# dc-dc_eth.net
KiCad netlist of a schematic drawn in Altium Designer
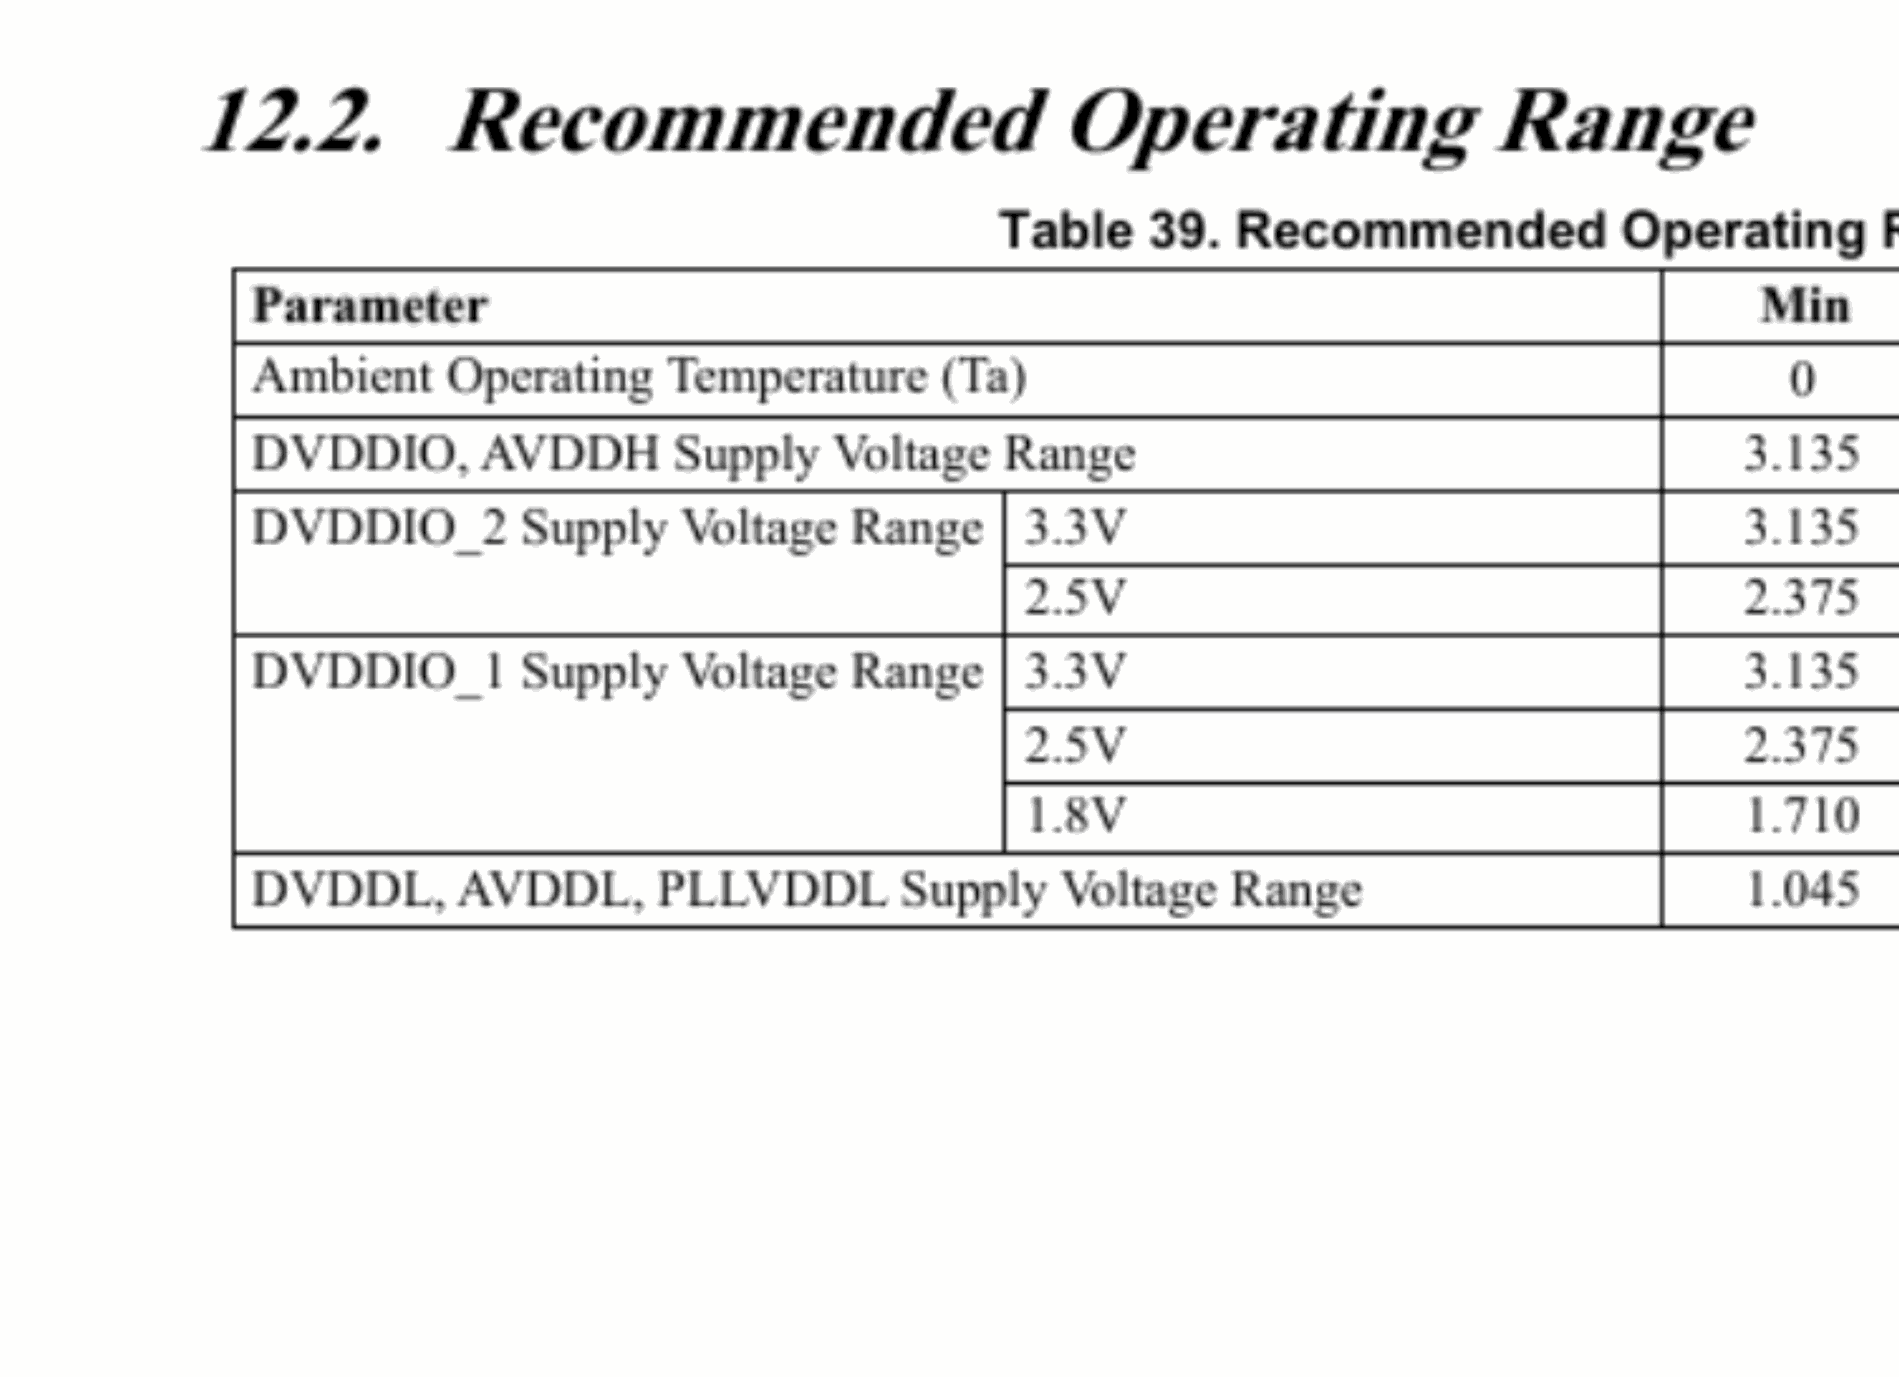
[diagram p0: dc-dc_eth.SchDoc, top left]
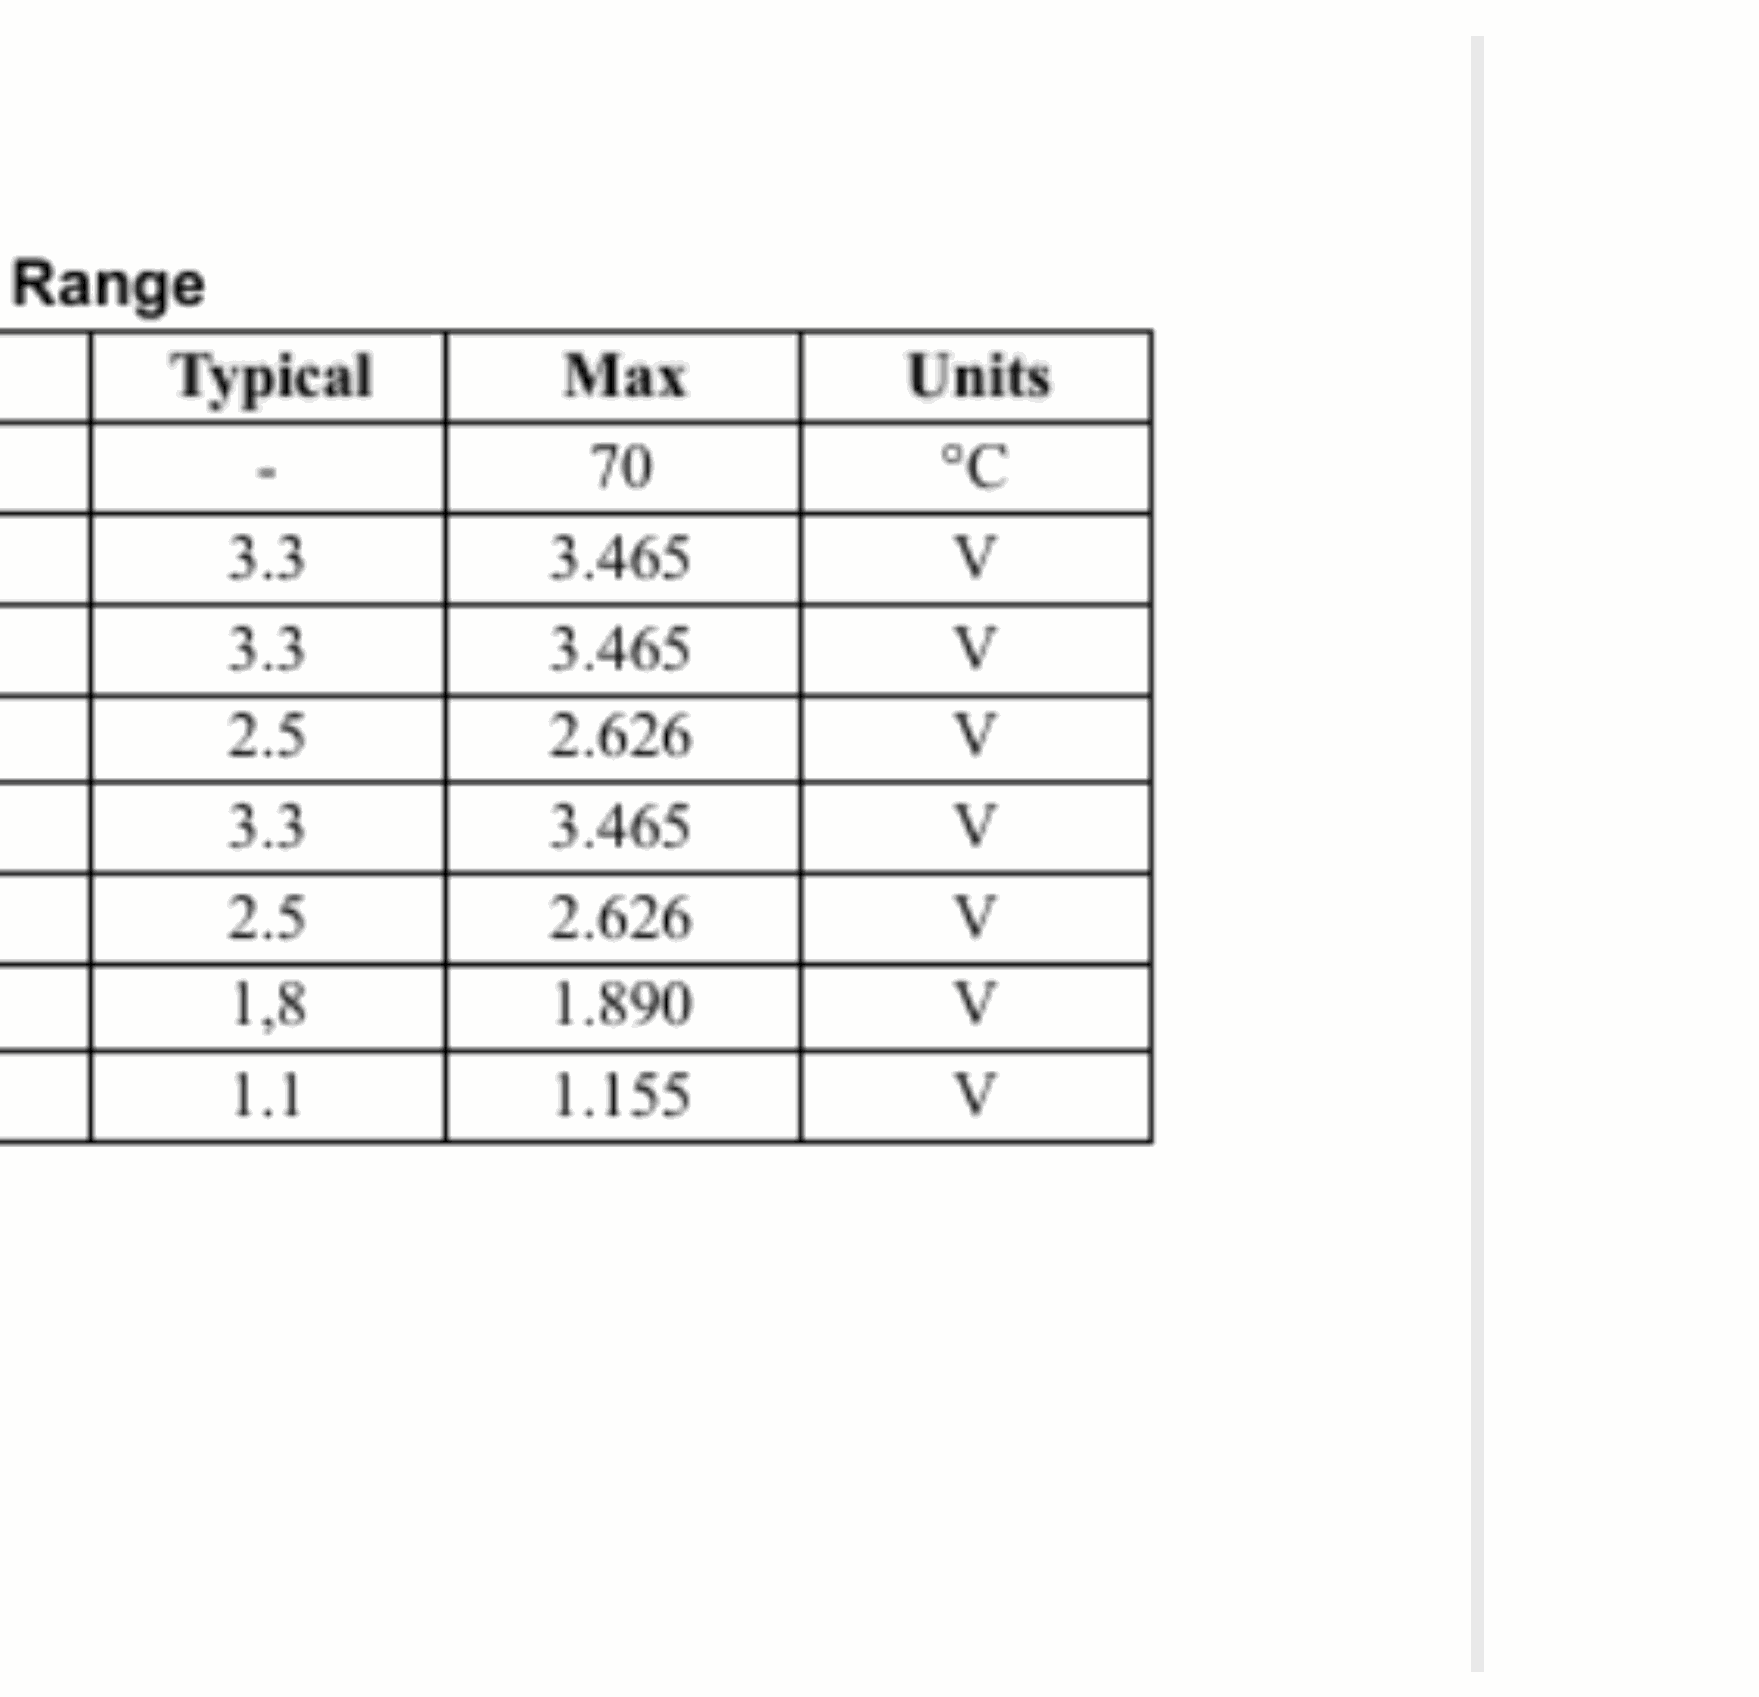
[diagram p1: dc-dc_eth.SchDoc, top right]
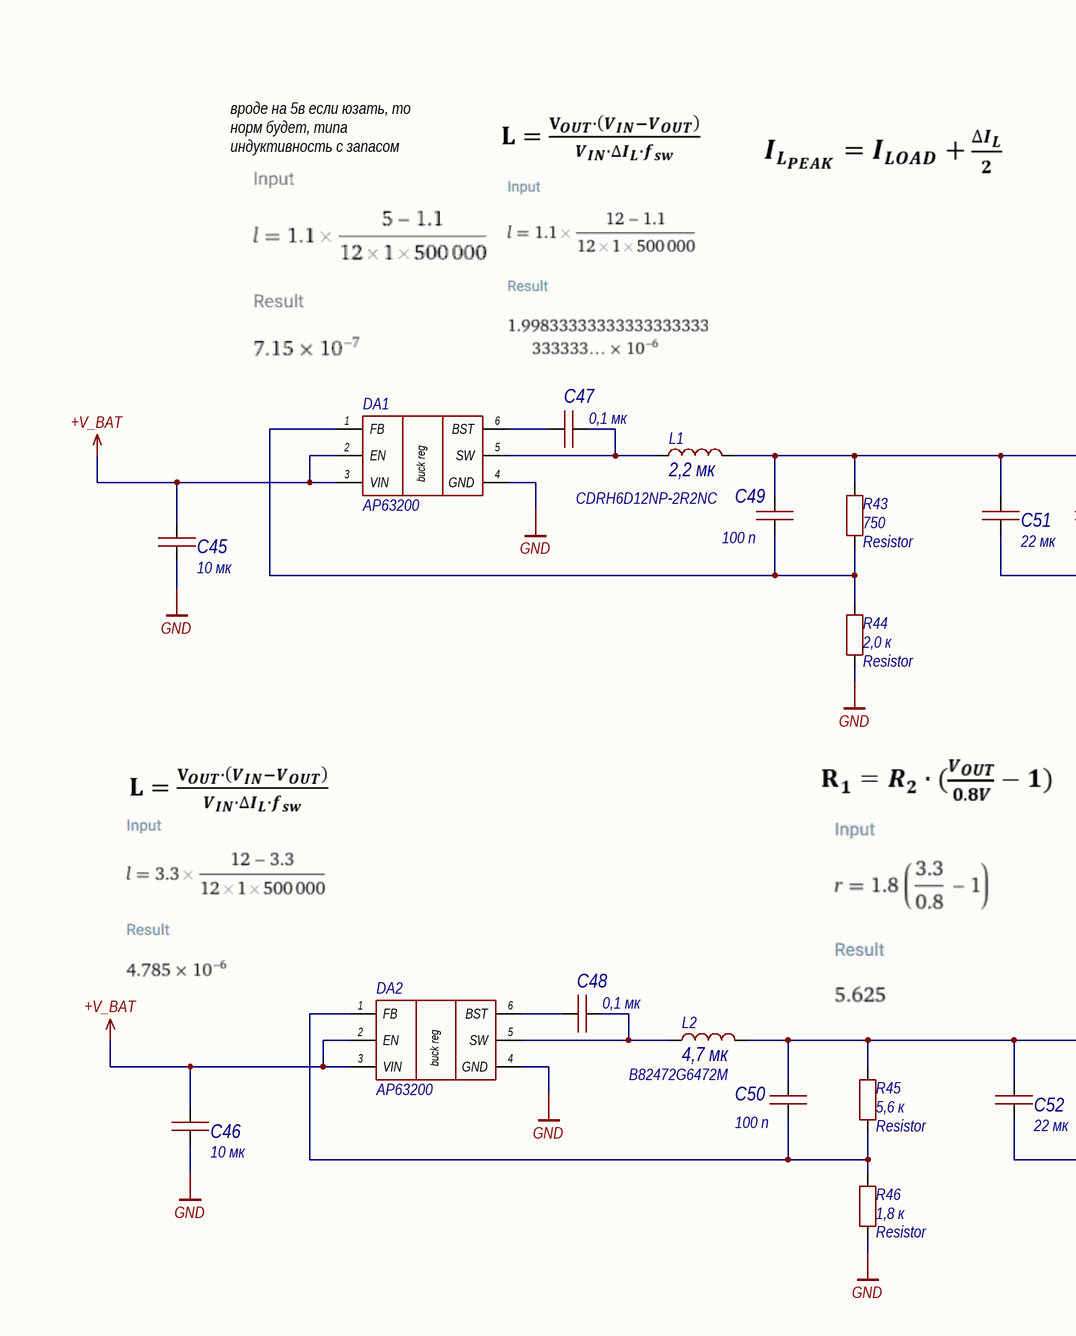
[diagram p2: dc-dc_eth.SchDoc, bottom left]
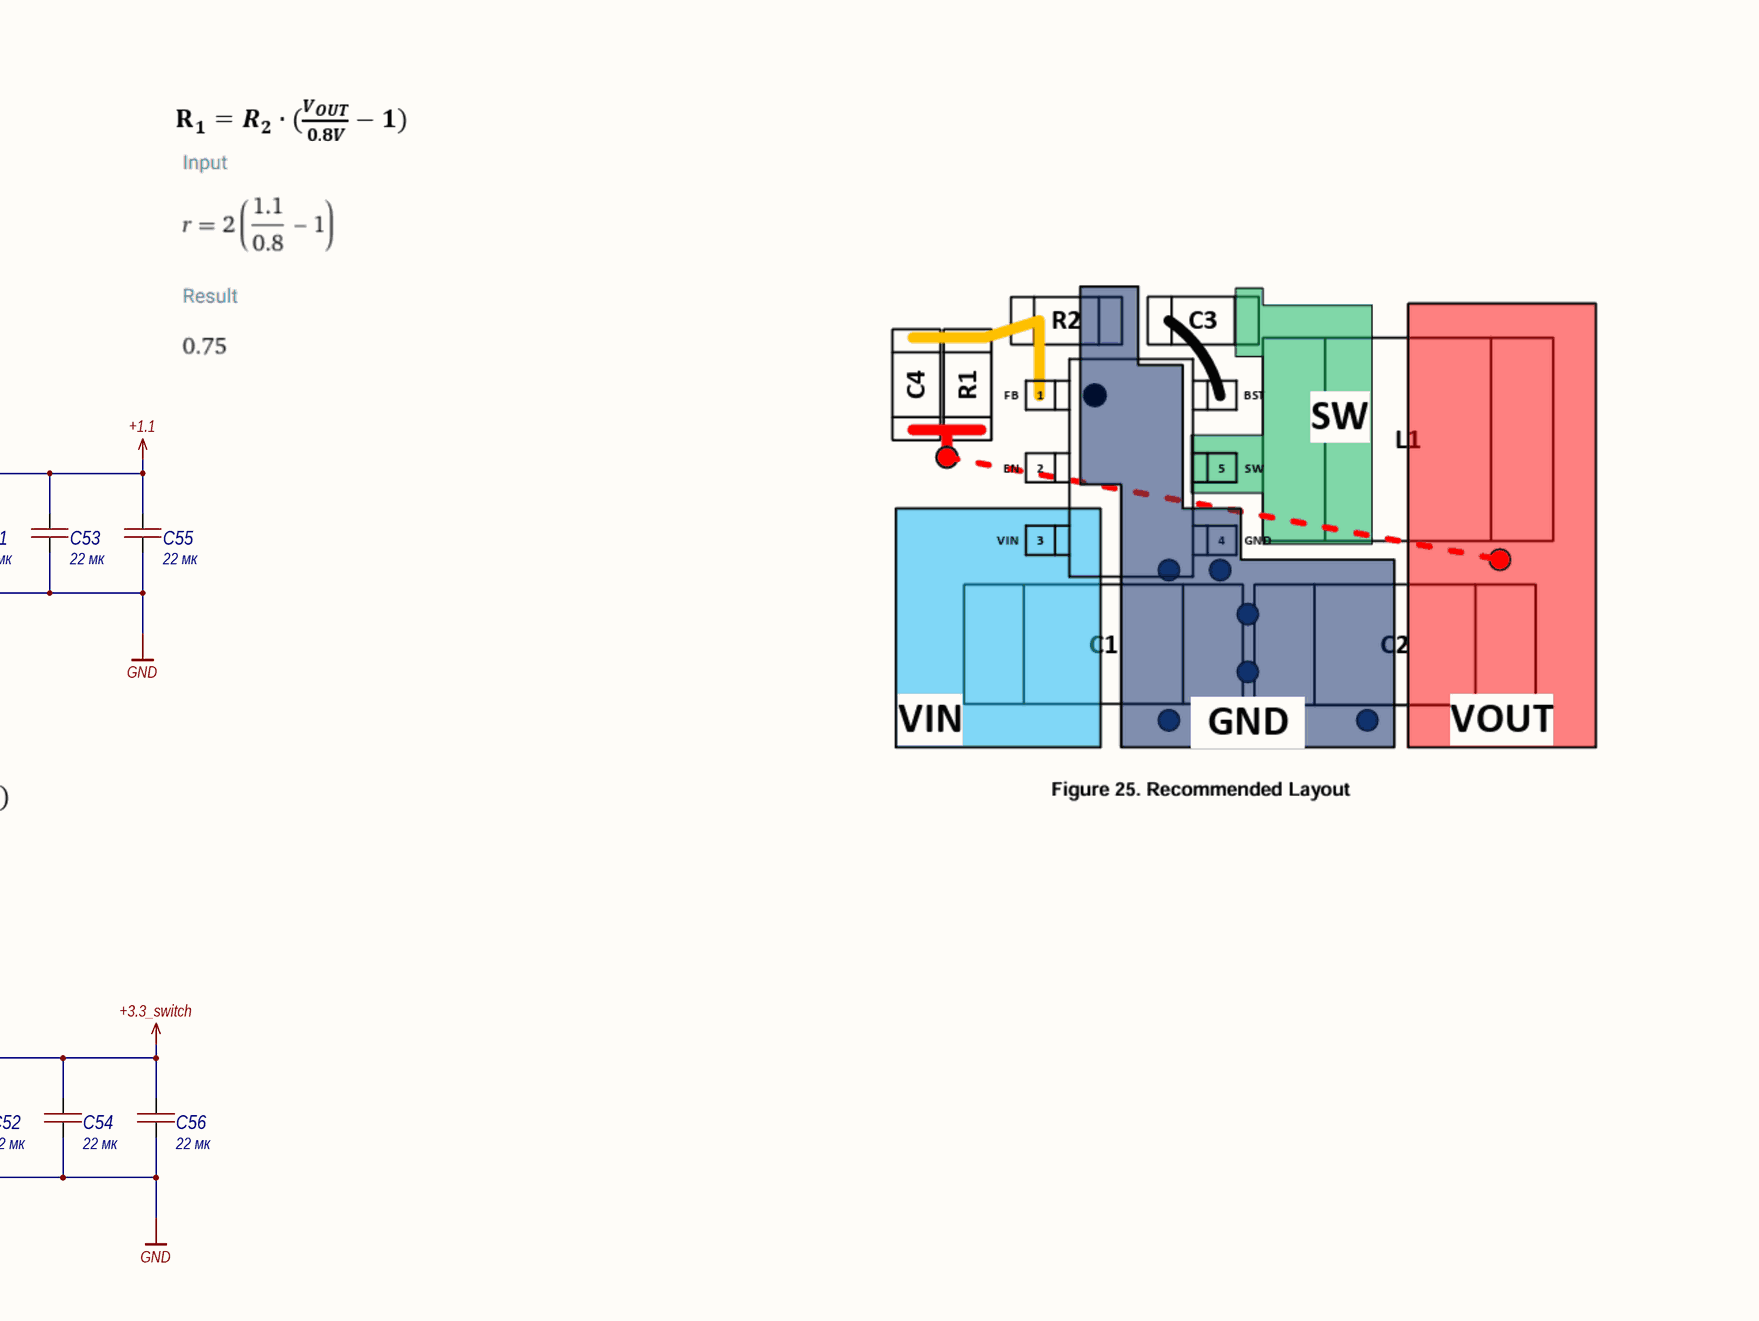
[diagram p3: dc-dc_eth.SchDoc, bottom right]

(export (version "E")
  (design (tool "Eeschema 10.0.6"))
  (components
    (comp (ref "C45")
      (value "10 мк")
      (footprint "1210C")
      (description "Конденсатор")
      (fields (field (name "PART NUMBER") "Capacitor_10u_10_35V_X7R_1210C") (field (name "TOLERANCE") "0,1"))
      (libsource (lib "Hydrolib") (part "Capacitor"))
    )
    (comp (ref "C46")
      (value "10 мк")
      (footprint "1210C")
      (description "Конденсатор")
      (fields (field (name "PART NUMBER") "Capacitor_10u_10_35V_X7R_1210C") (field (name "TOLERANCE") "0,1"))
      (libsource (lib "Hydrolib") (part "Capacitor"))
    )
    (comp (ref "C47")
      (value "0,1 мк")
      (footprint "0603C")
      (description "Конденсатор")
      (fields (field (name "PART NUMBER") "Capacitor_0,1u_10_50V_X7R_0603C") (field (name "TOLERANCE") "0,1"))
      (libsource (lib "Hydrolib") (part "Capacitor"))
    )
    (comp (ref "C48")
      (value "0,1 мк")
      (footprint "0603C")
      (description "Конденсатор")
      (fields (field (name "PART NUMBER") "Capacitor_0,1u_10_50V_X7R_0603C") (field (name "TOLERANCE") "0,1"))
      (libsource (lib "Hydrolib") (part "Capacitor"))
    )
    (comp (ref "C49")
      (value "100 п")
      (footprint "0603C")
      (description "Конденсатор")
      (fields (field (name "PART NUMBER") "Capacitor_100p_10_50V_X7R_0603C") (field (name "TOLERANCE") "0,1"))
      (libsource (lib "Hydrolib") (part "Capacitor"))
    )
    (comp (ref "C50")
      (value "100 п")
      (footprint "0603C")
      (description "Конденсатор")
      (fields (field (name "PART NUMBER") "Capacitor_100p_10_50V_X7R_0603C") (field (name "TOLERANCE") "0,1"))
      (libsource (lib "Hydrolib") (part "Capacitor"))
    )
    (comp (ref "C51")
      (value "22 мк")
      (footprint "1210C")
      (description "Конденсатор")
      (fields (field (name "PART NUMBER") "Capacitor_22u_10_25V_X7R_1210C") (field (name "TOLERANCE") "0,1"))
      (libsource (lib "Hydrolib") (part "Capacitor"))
    )
    (comp (ref "C52")
      (value "22 мк")
      (footprint "1210C")
      (description "Конденсатор")
      (fields (field (name "PART NUMBER") "Capacitor_22u_10_25V_X7R_1210C") (field (name "TOLERANCE") "0,1"))
      (libsource (lib "Hydrolib") (part "Capacitor"))
    )
    (comp (ref "C53")
      (value "22 мк")
      (footprint "1210C")
      (description "Конденсатор")
      (fields (field (name "PART NUMBER") "Capacitor_22u_10_25V_X7R_1210C") (field (name "TOLERANCE") "0,1"))
      (libsource (lib "Hydrolib") (part "Capacitor"))
    )
    (comp (ref "C54")
      (value "22 мк")
      (footprint "1210C")
      (description "Конденсатор")
      (fields (field (name "PART NUMBER") "Capacitor_22u_10_25V_X7R_1210C") (field (name "TOLERANCE") "0,1"))
      (libsource (lib "Hydrolib") (part "Capacitor"))
    )
    (comp (ref "C55")
      (value "22 мк")
      (footprint "1210C")
      (description "Конденсатор")
      (fields (field (name "PART NUMBER") "Capacitor_22u_10_25V_X7R_1210C") (field (name "TOLERANCE") "0,1"))
      (libsource (lib "Hydrolib") (part "Capacitor"))
    )
    (comp (ref "C56")
      (value "22 мк")
      (footprint "1210C")
      (description "Конденсатор")
      (fields (field (name "PART NUMBER") "Capacitor_22u_10_25V_X7R_1210C") (field (name "TOLERANCE") "0,1"))
      (libsource (lib "Hydrolib") (part "Capacitor"))
    )
    (comp (ref "DA1")
      (value "AP63200")
      (footprint "TSOT26")
      (description "DC-DC понижающий преобразователь, Vin: 3.8 - 40 В, adj, 2 А")
      (libsource (lib "Hydrolib") (part "AP63200"))
    )
    (comp (ref "DA2")
      (value "AP63200")
      (footprint "TSOT26")
      (description "DC-DC понижающий преобразователь, Vin: 3.8 - 40 В, adj, 2 А")
      (libsource (lib "Hydrolib") (part "AP63200"))
    )
    (comp (ref "L1")
      (value "CDRH6D12NP-2R2NC")
      (footprint "CDRH6D12")
      (description "Индуктивность на 2,2 мкГн, номинальный ток 2,5 А")
      (fields (field (name "ALTIUM_VALUE") "2,2 мк"))
      (libsource (lib "Hydrolib") (part "Inductance_1-3"))
    )
    (comp (ref "L2")
      (value "B82472G6472M")
      (footprint "B82462G4")
      (description "Индуктивность на 4,7 мкГн, номинальный ток 2,5 А")
      (fields (field (name "ALTIUM_VALUE") "4,7 мк"))
      (libsource (lib "Hydrolib") (part "Inductance"))
    )
    (comp (ref "R43")
      (value "Resistor")
      (footprint "0603R")
      (description "Резистор номиналом 750 Ом 1%")
      (fields
        (field (name "ALTIUM_VALUE") "750")
        (field (name "PART NUMBER") "Resistor_750_1_0603")
        (field (name "TOLERANCE") "1%")
      )
      (libsource (lib "Hydrolib") (part "Resistor"))
    )
    (comp (ref "R44")
      (value "Resistor")
      (footprint "0603R")
      (description "Резистор номиналом 2,0 кОм 1%")
      (fields
        (field (name "ALTIUM_VALUE") "2,0 к")
        (field (name "PART NUMBER") "Resistor_2.0k_1_0603")
        (field (name "TOLERANCE") "1%")
      )
      (libsource (lib "Hydrolib") (part "Resistor"))
    )
    (comp (ref "R45")
      (value "Resistor")
      (footprint "0603R")
      (description "Резистор номиналом 5,6 кОм 1%")
      (fields
        (field (name "ALTIUM_VALUE") "5,6 к")
        (field (name "PART NUMBER") "Resistor_5.6k_1_0603")
        (field (name "TOLERANCE") "1%")
      )
      (libsource (lib "Hydrolib") (part "Resistor"))
    )
    (comp (ref "R46")
      (value "Resistor")
      (footprint "0603R")
      (description "Резистор номиналом 1,8 кОм 1%")
      (fields
        (field (name "ALTIUM_VALUE") "1,8 к")
        (field (name "PART NUMBER") "Resistor_1.8k_1_0603")
        (field (name "TOLERANCE") "1%")
      )
      (libsource (lib "Hydrolib") (part "Resistor"))
    )
  )
  (nets
    (net (code "1") (name "+1.1") (class "Default")
      (node (ref "C49") (pin "2") (pinfunction "2_2") (pintype "passive"))
      (node (ref "C51") (pin "2") (pinfunction "2_2") (pintype "passive"))
      (node (ref "C53") (pin "2") (pinfunction "2_2") (pintype "passive"))
      (node (ref "C55") (pin "2") (pinfunction "2_2") (pintype "passive"))
      (node (ref "L1") (pin "3") (pinfunction "3_3") (pintype "passive"))
      (node (ref "R43") (pin "2") (pinfunction "2_2") (pintype "passive"))
    )
    (net (code "2") (name "+3.3_switch") (class "Default")
      (node (ref "C50") (pin "2") (pinfunction "2_2") (pintype "passive"))
      (node (ref "C52") (pin "2") (pinfunction "2_2") (pintype "passive"))
      (node (ref "C54") (pin "2") (pinfunction "2_2") (pintype "passive"))
      (node (ref "C56") (pin "2") (pinfunction "2_2") (pintype "passive"))
      (node (ref "L2") (pin "2") (pinfunction "2_2") (pintype "passive"))
      (node (ref "R45") (pin "2") (pinfunction "2_2") (pintype "passive"))
    )
    (net (code "3") (name "+V_BAT") (class "Default")
      (node (ref "C45") (pin "2") (pinfunction "2_2") (pintype "passive"))
      (node (ref "C46") (pin "2") (pinfunction "2_2") (pintype "passive"))
      (node (ref "DA1") (pin "2") (pinfunction "EN_2") (pintype "passive"))
      (node (ref "DA1") (pin "3") (pinfunction "VIN_3") (pintype "passive"))
      (node (ref "DA2") (pin "2") (pinfunction "EN_2") (pintype "passive"))
      (node (ref "DA2") (pin "3") (pinfunction "VIN_3") (pintype "passive"))
    )
    (net (code "4") (name "GND") (class "Default")
      (node (ref "C45") (pin "1") (pinfunction "1_1") (pintype "passive"))
      (node (ref "C46") (pin "1") (pinfunction "1_1") (pintype "passive"))
      (node (ref "C51") (pin "1") (pinfunction "1_1") (pintype "passive"))
      (node (ref "C52") (pin "1") (pinfunction "1_1") (pintype "passive"))
      (node (ref "C53") (pin "1") (pinfunction "1_1") (pintype "passive"))
      (node (ref "C54") (pin "1") (pinfunction "1_1") (pintype "passive"))
      (node (ref "C55") (pin "1") (pinfunction "1_1") (pintype "passive"))
      (node (ref "C56") (pin "1") (pinfunction "1_1") (pintype "passive"))
      (node (ref "DA1") (pin "4") (pinfunction "GND_4") (pintype "passive"))
      (node (ref "DA2") (pin "4") (pinfunction "GND_4") (pintype "passive"))
      (node (ref "R44") (pin "1") (pinfunction "1_1") (pintype "passive"))
      (node (ref "R46") (pin "1") (pinfunction "1_1") (pintype "passive"))
    )
    (net (code "5") (name "Net-(DA1-BST)") (class "Default")
      (node (ref "C47") (pin "1") (pinfunction "1_1") (pintype "passive"))
      (node (ref "DA1") (pin "6") (pinfunction "BST_6") (pintype "passive"))
    )
    (net (code "6") (name "Net-(DA1-FB)") (class "Default")
      (node (ref "C49") (pin "1") (pinfunction "1_1") (pintype "passive"))
      (node (ref "DA1") (pin "1") (pinfunction "FB_1") (pintype "passive"))
      (node (ref "R43") (pin "1") (pinfunction "1_1") (pintype "passive"))
      (node (ref "R44") (pin "2") (pinfunction "2_2") (pintype "passive"))
    )
    (net (code "7") (name "Net-(DA1-SW)") (class "Default")
      (node (ref "C47") (pin "2") (pinfunction "2_2") (pintype "passive"))
      (node (ref "DA1") (pin "5") (pinfunction "SW_5") (pintype "passive"))
      (node (ref "L1") (pin "1") (pinfunction "1_1") (pintype "passive"))
    )
    (net (code "8") (name "Net-(DA2-BST)") (class "Default")
      (node (ref "C48") (pin "1") (pinfunction "1_1") (pintype "passive"))
      (node (ref "DA2") (pin "6") (pinfunction "BST_6") (pintype "passive"))
    )
    (net (code "9") (name "Net-(DA2-FB)") (class "Default")
      (node (ref "C50") (pin "1") (pinfunction "1_1") (pintype "passive"))
      (node (ref "DA2") (pin "1") (pinfunction "FB_1") (pintype "passive"))
      (node (ref "R45") (pin "1") (pinfunction "1_1") (pintype "passive"))
      (node (ref "R46") (pin "2") (pinfunction "2_2") (pintype "passive"))
    )
    (net (code "10") (name "Net-(DA2-SW)") (class "Default")
      (node (ref "C48") (pin "2") (pinfunction "2_2") (pintype "passive"))
      (node (ref "DA2") (pin "5") (pinfunction "SW_5") (pintype "passive"))
      (node (ref "L2") (pin "1") (pinfunction "1_1") (pintype "passive"))
    )
  )
)
